# schematic.net
KiCad netlist of a schematic drawn in EasyEDA
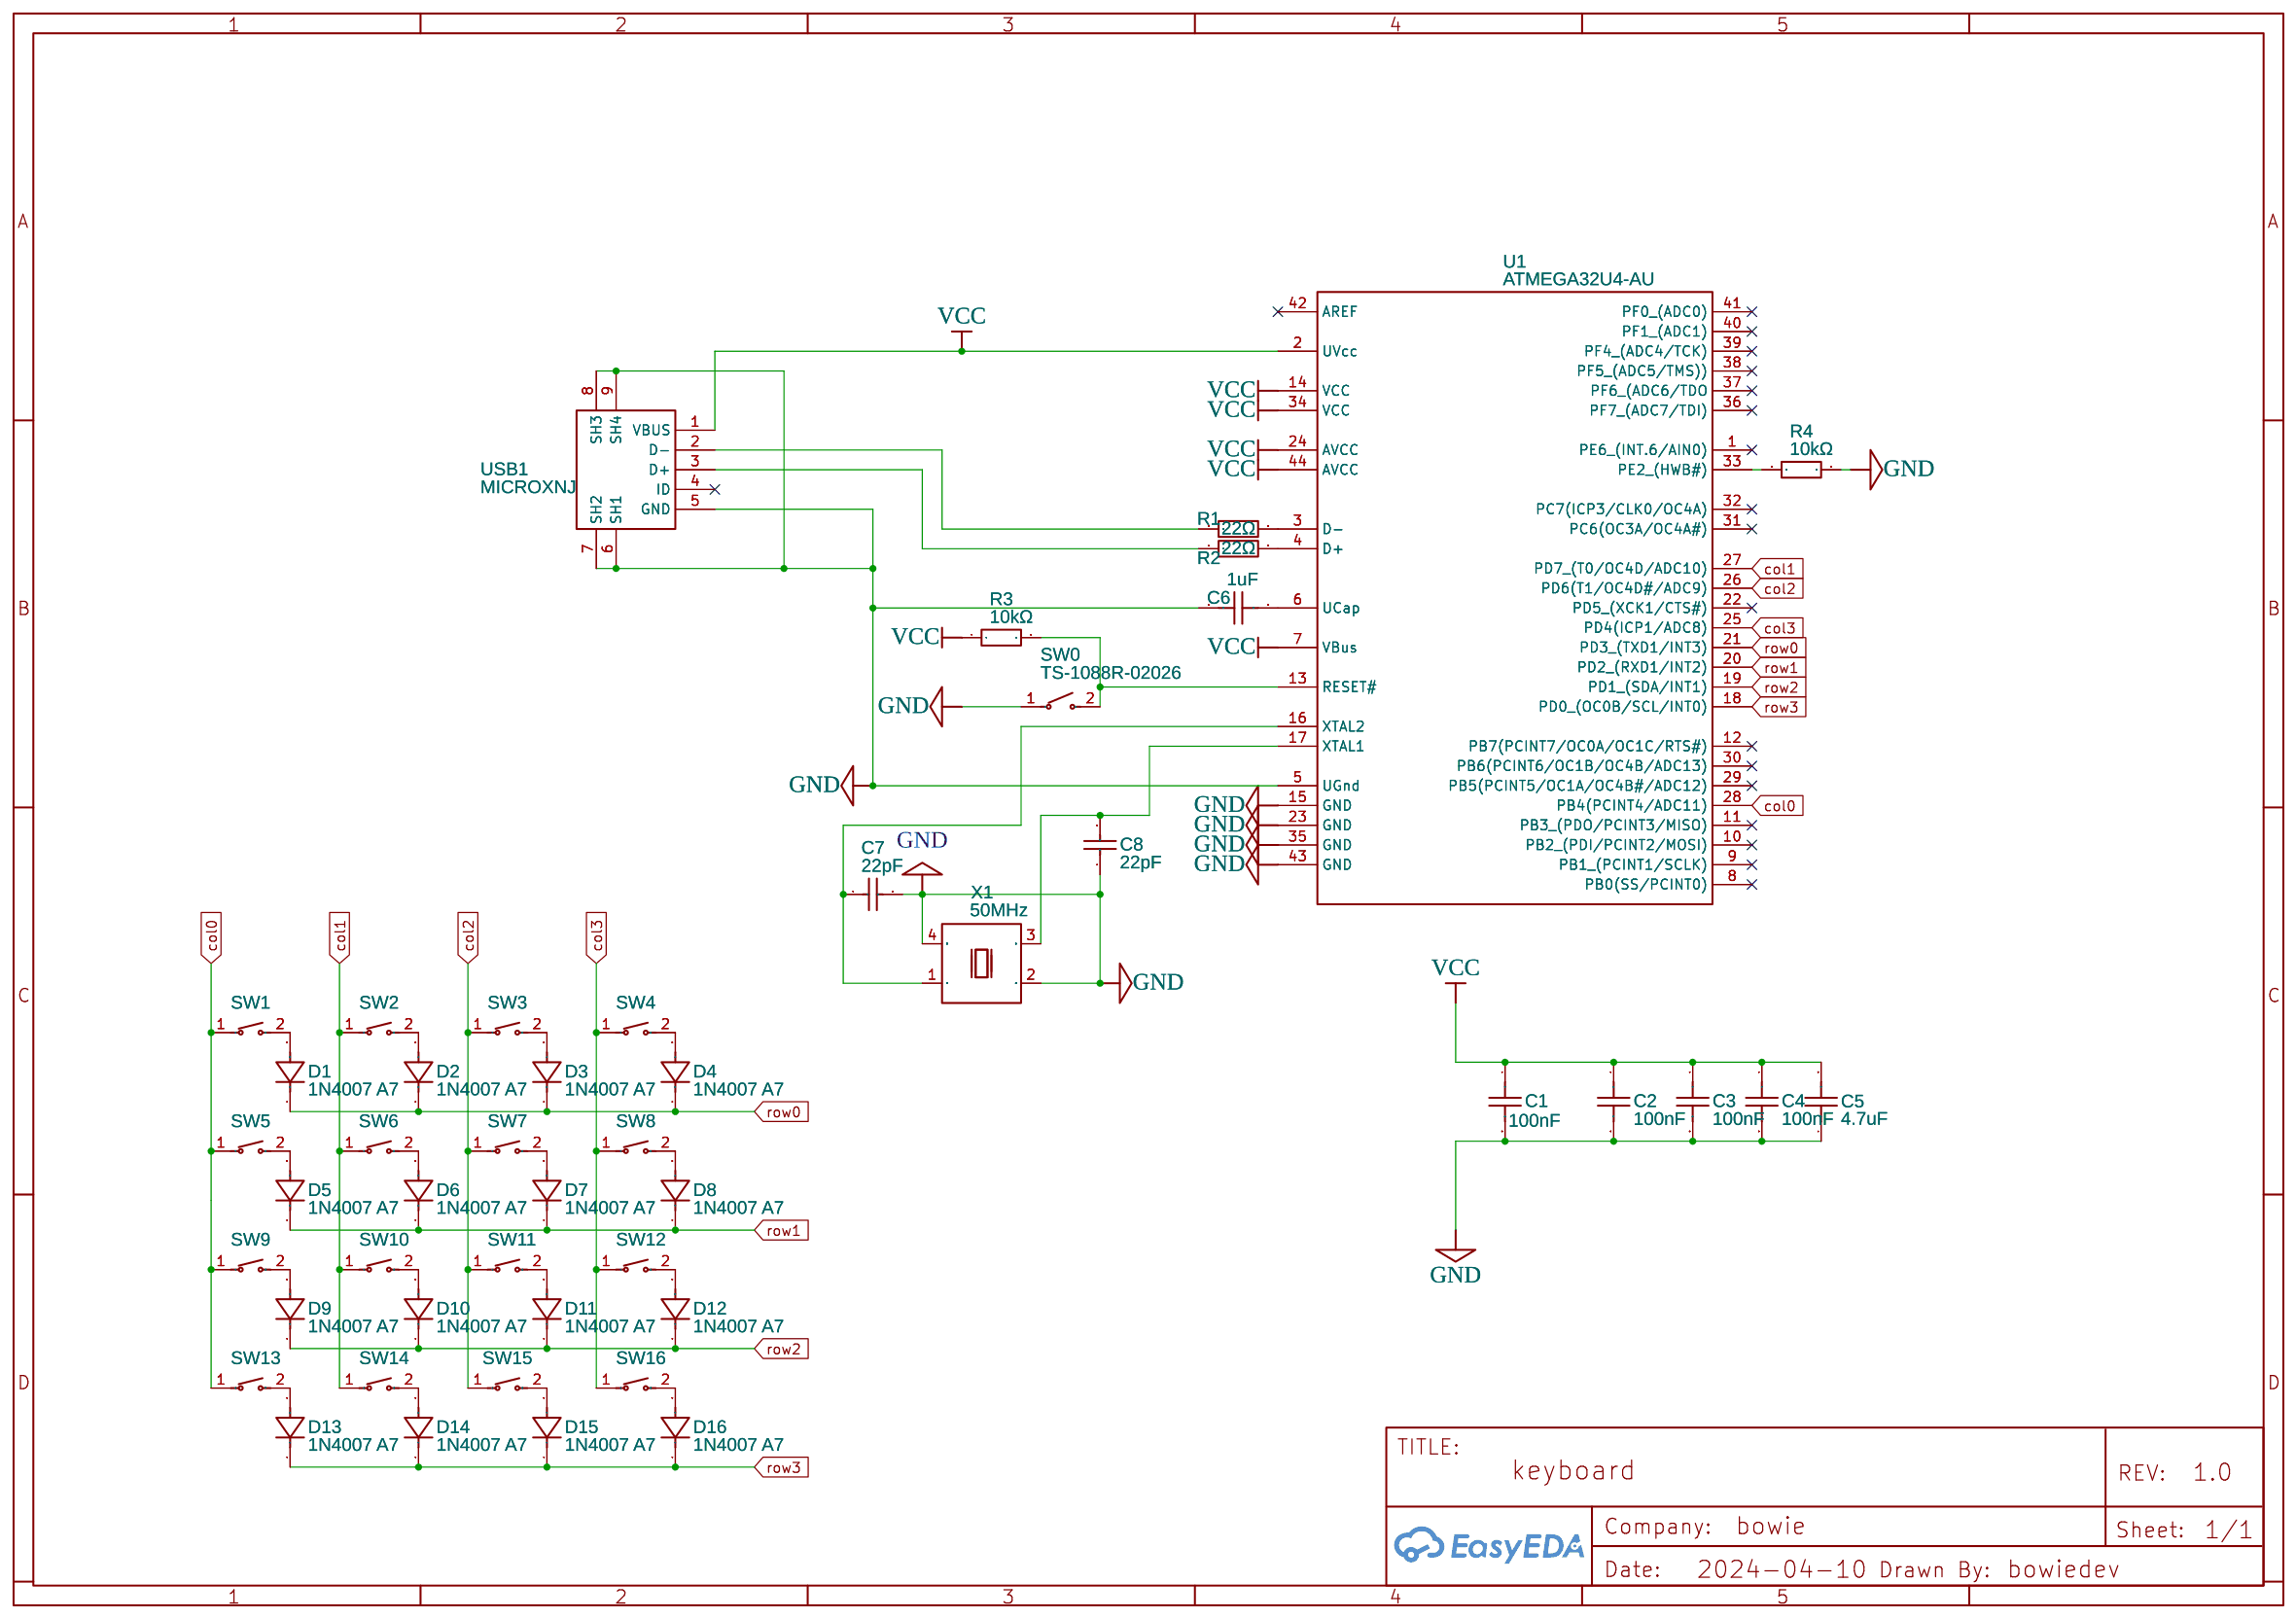
[diagram p0: schematic sheet]

(export (version "E")
  (design (tool "Eeschema 10.0.6"))
  (components
    (comp (ref "C1")
      (value "100nF")
      (fields (field (name "Manufacturer Part") "C1005X7R1C104KT000F") (field (name "Manufacturer") "TDK"))
      (libsource (lib "") (part "C1005X7R1C104KT000F"))
    )
    (comp (ref "C2")
      (value "100nF")
      (fields (field (name "Manufacturer Part") "C1005X7R1C104KT000F") (field (name "Manufacturer") "TDK"))
      (libsource (lib "") (part "C1005X7R1C104KT000F"))
    )
    (comp (ref "C3")
      (value "100nF")
      (fields (field (name "Manufacturer Part") "C1005X7R1C104KT000F") (field (name "Manufacturer") "TDK"))
      (libsource (lib "") (part "C1005X7R1C104KT000F"))
    )
    (comp (ref "C4")
      (value "100nF")
      (fields (field (name "Manufacturer Part") "C1005X7R1C104KT000F") (field (name "Manufacturer") "TDK"))
      (libsource (lib "") (part "C1005X7R1C104KT000F"))
    )
    (comp (ref "C5")
      (value "4.7uF")
      (fields
        (field (name "Manufacturer Part") "CS2012X5R475K500NRE")
        (field (name "Manufacturer") "SAMWHA(三和)")
      )
      (libsource (lib "") (part "CS2012X5R475K500NRE"))
    )
    (comp (ref "C6")
      (value "1uF")
      (fields
        (field (name "Manufacturer Part") "CS1608X7R105K250NRB")
        (field (name "Manufacturer") "SAMWHA(三和)")
      )
      (libsource (lib "") (part "CS1608X7R105K250NRB"))
    )
    (comp (ref "C7")
      (value "22pF")
      (fields (field (name "Manufacturer Part") "0402CG220J500NT") (field (name "Manufacturer") "FH(风华)"))
      (libsource (lib "") (part "0402CG220J500NT"))
    )
    (comp (ref "C8")
      (value "22pF")
      (fields (field (name "Manufacturer Part") "0402CG220J500NT") (field (name "Manufacturer") "FH(风华)"))
      (libsource (lib "") (part "0402CG220J500NT_1"))
    )
    (comp (ref "D1")
      (value "1N4007 A7")
      (fields (field (name "Manufacturer") "MSKSEMI(美森科)"))
      (libsource (lib "") (part "1N4007 A7"))
    )
    (comp (ref "D2")
      (value "1N4007 A7")
      (fields (field (name "Manufacturer") "MSKSEMI(美森科)"))
      (libsource (lib "") (part "1N4007 A7"))
    )
    (comp (ref "D3")
      (value "1N4007 A7")
      (fields (field (name "Manufacturer") "MSKSEMI(美森科)"))
      (libsource (lib "") (part "1N4007 A7"))
    )
    (comp (ref "D4")
      (value "1N4007 A7")
      (fields (field (name "Manufacturer") "MSKSEMI(美森科)"))
      (libsource (lib "") (part "1N4007 A7"))
    )
    (comp (ref "D5")
      (value "1N4007 A7")
      (fields (field (name "Manufacturer") "MSKSEMI(美森科)"))
      (libsource (lib "") (part "1N4007 A7"))
    )
    (comp (ref "D6")
      (value "1N4007 A7")
      (fields (field (name "Manufacturer") "MSKSEMI(美森科)"))
      (libsource (lib "") (part "1N4007 A7"))
    )
    (comp (ref "D7")
      (value "1N4007 A7")
      (fields (field (name "Manufacturer") "MSKSEMI(美森科)"))
      (libsource (lib "") (part "1N4007 A7"))
    )
    (comp (ref "D8")
      (value "1N4007 A7")
      (fields (field (name "Manufacturer") "MSKSEMI(美森科)"))
      (libsource (lib "") (part "1N4007 A7"))
    )
    (comp (ref "D9")
      (value "1N4007 A7")
      (fields (field (name "Manufacturer") "MSKSEMI(美森科)"))
      (libsource (lib "") (part "1N4007 A7"))
    )
    (comp (ref "D10")
      (value "1N4007 A7")
      (fields (field (name "Manufacturer") "MSKSEMI(美森科)"))
      (libsource (lib "") (part "1N4007 A7"))
    )
    (comp (ref "D11")
      (value "1N4007 A7")
      (fields (field (name "Manufacturer") "MSKSEMI(美森科)"))
      (libsource (lib "") (part "1N4007 A7"))
    )
    (comp (ref "D12")
      (value "1N4007 A7")
      (fields (field (name "Manufacturer") "MSKSEMI(美森科)"))
      (libsource (lib "") (part "1N4007 A7"))
    )
    (comp (ref "D13")
      (value "1N4007 A7")
      (fields (field (name "Manufacturer") "MSKSEMI(美森科)"))
      (libsource (lib "") (part "1N4007 A7"))
    )
    (comp (ref "D14")
      (value "1N4007 A7")
      (fields (field (name "Manufacturer") "MSKSEMI(美森科)"))
      (libsource (lib "") (part "1N4007 A7"))
    )
    (comp (ref "D15")
      (value "1N4007 A7")
      (fields (field (name "Manufacturer") "MSKSEMI(美森科)"))
      (libsource (lib "") (part "1N4007 A7"))
    )
    (comp (ref "D16")
      (value "1N4007 A7")
      (fields (field (name "Manufacturer") "MSKSEMI(美森科)"))
      (libsource (lib "") (part "1N4007 A7"))
    )
    (comp (ref "R1")
      (value "22Ω")
      (fields
        (field (name "Manufacturer Part") "0805W8J0220T5E")
        (field (name "Manufacturer") "UNI-ROYAL(厚声)")
      )
      (libsource (lib "") (part "0805W8J0220T5E"))
    )
    (comp (ref "R2")
      (value "22Ω")
      (fields
        (field (name "Manufacturer Part") "0805W8J0220T5E")
        (field (name "Manufacturer") "UNI-ROYAL(厚声)")
      )
      (libsource (lib "") (part "0805W8J0220T5E"))
    )
    (comp (ref "R3")
      (value "10kΩ")
      (fields
        (field (name "Manufacturer Part") "0805W8F1002T5E")
        (field (name "Manufacturer") "UNI-ROYAL(厚声)")
      )
      (libsource (lib "") (part "0805W8F1002T5E"))
    )
    (comp (ref "R4")
      (value "10kΩ")
      (fields
        (field (name "Manufacturer Part") "0805W8F1002T5E")
        (field (name "Manufacturer") "UNI-ROYAL(厚声)")
      )
      (libsource (lib "") (part "0805W8F1002T5E"))
    )
    (comp (ref "SW0")
      (value "TS-1088R-02026")
      (fields (field (name "Manufacturer") "XUNPU(讯普)"))
      (libsource (lib "") (part "TS-1088R-02026"))
    )
    (comp (ref "SW1")
      (value "CPG151101D93")
      (fields (field (name "Manufacturer") "Kailh(凯华)"))
      (libsource (lib "") (part "CPG151101D93"))
    )
    (comp (ref "SW2")
      (value "CPG151101D93")
      (fields (field (name "Manufacturer") "Kailh(凯华)"))
      (libsource (lib "") (part "CPG151101D93"))
    )
    (comp (ref "SW3")
      (value "CPG151101D93")
      (fields (field (name "Manufacturer") "Kailh(凯华)"))
      (libsource (lib "") (part "CPG151101D93"))
    )
    (comp (ref "SW4")
      (value "CPG151101D93")
      (fields (field (name "Manufacturer") "Kailh(凯华)"))
      (libsource (lib "") (part "CPG151101D93"))
    )
    (comp (ref "SW5")
      (value "CPG151101D93")
      (fields (field (name "Manufacturer") "Kailh(凯华)"))
      (libsource (lib "") (part "CPG151101D93"))
    )
    (comp (ref "SW6")
      (value "CPG151101D93")
      (fields (field (name "Manufacturer") "Kailh(凯华)"))
      (libsource (lib "") (part "CPG151101D93"))
    )
    (comp (ref "SW7")
      (value "CPG151101D93")
      (fields (field (name "Manufacturer") "Kailh(凯华)"))
      (libsource (lib "") (part "CPG151101D93"))
    )
    (comp (ref "SW8")
      (value "CPG151101D93")
      (fields (field (name "Manufacturer") "Kailh(凯华)"))
      (libsource (lib "") (part "CPG151101D93"))
    )
    (comp (ref "SW9")
      (value "CPG151101D93")
      (fields (field (name "Manufacturer") "Kailh(凯华)"))
      (libsource (lib "") (part "CPG151101D93"))
    )
    (comp (ref "SW10")
      (value "CPG151101D93")
      (fields (field (name "Manufacturer") "Kailh(凯华)"))
      (libsource (lib "") (part "CPG151101D93"))
    )
    (comp (ref "SW11")
      (value "CPG151101D93")
      (fields (field (name "Manufacturer") "Kailh(凯华)"))
      (libsource (lib "") (part "CPG151101D93"))
    )
    (comp (ref "SW12")
      (value "CPG151101D93")
      (fields (field (name "Manufacturer") "Kailh(凯华)"))
      (libsource (lib "") (part "CPG151101D93"))
    )
    (comp (ref "SW13")
      (value "CPG151101D93")
      (fields (field (name "Manufacturer") "Kailh(凯华)"))
      (libsource (lib "") (part "CPG151101D93"))
    )
    (comp (ref "SW14")
      (value "CPG151101D93")
      (fields (field (name "Manufacturer") "Kailh(凯华)"))
      (libsource (lib "") (part "CPG151101D93"))
    )
    (comp (ref "SW15")
      (value "CPG151101D93")
      (fields (field (name "Manufacturer") "Kailh(凯华)"))
      (libsource (lib "") (part "CPG151101D93"))
    )
    (comp (ref "SW16")
      (value "CPG151101D93")
      (fields (field (name "Manufacturer") "Kailh(凯华)"))
      (libsource (lib "") (part "CPG151101D93"))
    )
    (comp (ref "U1")
      (value "ATMEGA32U4-AU")
      (fields (field (name "Manufacturer") "MICROCHIP(美国微芯)"))
      (libsource (lib "") (part "ATMEGA32U4-AU"))
    )
    (comp (ref "USB1")
      (value "MICROXNJ")
      (fields (field (name "Manufacturer Part") "MicroXNJ") (field (name "Manufacturer") "SHOU HAN(首韩)"))
      (libsource (lib "") (part "MICROXNJ"))
    )
    (comp (ref "X1")
      (value "50MHz")
      (fields
        (field (name "Manufacturer Part") "OVETGLJTNF-50MHZ")
        (field (name "Manufacturer") "TAITIEN(泰艺电子)")
      )
      (libsource (lib "") (part "OVETGLJTNF-50MHZ"))
    )
  )
  (nets
    (net (code "1") (name "GND") (class "Default")
      (node (ref "C1") (pin "2") (pinfunction "2_2") (pintype "unspecified"))
      (node (ref "C2") (pin "2") (pinfunction "2_2") (pintype "unspecified"))
      (node (ref "C3") (pin "2") (pinfunction "2_2") (pintype "unspecified"))
      (node (ref "C4") (pin "2") (pinfunction "2_2") (pintype "unspecified"))
      (node (ref "C5") (pin "1") (pinfunction "1_1") (pintype "unspecified"))
      (node (ref "C6") (pin "1") (pinfunction "1_1") (pintype "unspecified"))
      (node (ref "C7") (pin "2") (pinfunction "2_2") (pintype "input"))
      (node (ref "C8") (pin "1") (pinfunction "1_1") (pintype "input"))
      (node (ref "R4") (pin "2") (pinfunction "2_2") (pintype "input"))
      (node (ref "SW0") (pin "1") (pinfunction "1_1") (pintype "unspecified"))
      (node (ref "U1") (pin "15") (pinfunction "GND_15") (pintype "passive"))
      (node (ref "U1") (pin "23") (pinfunction "GND_23") (pintype "passive"))
      (node (ref "U1") (pin "35") (pinfunction "GND_35") (pintype "passive"))
      (node (ref "U1") (pin "43") (pinfunction "GND_43") (pintype "passive"))
      (node (ref "U1") (pin "5") (pinfunction "UGnd_5") (pintype "passive"))
      (node (ref "USB1") (pin "5") (pinfunction "GND_5") (pintype "unspecified"))
      (node (ref "USB1") (pin "6") (pinfunction "SH1_6") (pintype "unspecified"))
      (node (ref "USB1") (pin "7") (pinfunction "SH2_7") (pintype "unspecified"))
      (node (ref "USB1") (pin "8") (pinfunction "SH3_8") (pintype "unspecified"))
      (node (ref "USB1") (pin "9") (pinfunction "SH4_9") (pintype "unspecified"))
      (node (ref "X1") (pin "2") (pinfunction "GND_2") (pintype "unspecified"))
      (node (ref "X1") (pin "4") (pinfunction "VCC_4") (pintype "unspecified"))
    )
    (net (code "2") (name "Net-(D1-A)") (class "Default")
      (node (ref "D1") (pin "2") (pinfunction "A_2") (pintype "unspecified"))
      (node (ref "SW1") (pin "2") (pinfunction "2_2") (pintype "unspecified"))
    )
    (net (code "3") (name "Net-(D2-A)") (class "Default")
      (node (ref "D2") (pin "2") (pinfunction "A_2") (pintype "unspecified"))
      (node (ref "SW2") (pin "2") (pinfunction "2_2") (pintype "unspecified"))
    )
    (net (code "4") (name "Net-(D3-A)") (class "Default")
      (node (ref "D3") (pin "2") (pinfunction "A_2") (pintype "unspecified"))
      (node (ref "SW3") (pin "2") (pinfunction "2_2") (pintype "unspecified"))
    )
    (net (code "5") (name "Net-(D4-A)") (class "Default")
      (node (ref "D4") (pin "2") (pinfunction "A_2") (pintype "unspecified"))
      (node (ref "SW4") (pin "2") (pinfunction "2_2") (pintype "unspecified"))
    )
    (net (code "6") (name "Net-(D5-A)") (class "Default")
      (node (ref "D5") (pin "2") (pinfunction "A_2") (pintype "unspecified"))
      (node (ref "SW5") (pin "2") (pinfunction "2_2") (pintype "unspecified"))
    )
    (net (code "7") (name "Net-(D6-A)") (class "Default")
      (node (ref "D6") (pin "2") (pinfunction "A_2") (pintype "unspecified"))
      (node (ref "SW6") (pin "2") (pinfunction "2_2") (pintype "unspecified"))
    )
    (net (code "8") (name "Net-(D7-A)") (class "Default")
      (node (ref "D7") (pin "2") (pinfunction "A_2") (pintype "unspecified"))
      (node (ref "SW7") (pin "2") (pinfunction "2_2") (pintype "unspecified"))
    )
    (net (code "9") (name "Net-(D8-A)") (class "Default")
      (node (ref "D8") (pin "2") (pinfunction "A_2") (pintype "unspecified"))
      (node (ref "SW8") (pin "2") (pinfunction "2_2") (pintype "unspecified"))
    )
    (net (code "10") (name "Net-(D9-A)") (class "Default")
      (node (ref "D9") (pin "2") (pinfunction "A_2") (pintype "unspecified"))
      (node (ref "SW9") (pin "2") (pinfunction "2_2") (pintype "unspecified"))
    )
    (net (code "11") (name "Net-(D10-A)") (class "Default")
      (node (ref "D10") (pin "2") (pinfunction "A_2") (pintype "unspecified"))
      (node (ref "SW10") (pin "2") (pinfunction "2_2") (pintype "unspecified"))
    )
    (net (code "12") (name "Net-(D11-A)") (class "Default")
      (node (ref "D11") (pin "2") (pinfunction "A_2") (pintype "unspecified"))
      (node (ref "SW11") (pin "2") (pinfunction "2_2") (pintype "unspecified"))
    )
    (net (code "13") (name "Net-(D12-A)") (class "Default")
      (node (ref "D12") (pin "2") (pinfunction "A_2") (pintype "unspecified"))
      (node (ref "SW12") (pin "2") (pinfunction "2_2") (pintype "unspecified"))
    )
    (net (code "14") (name "Net-(D13-A)") (class "Default")
      (node (ref "D13") (pin "2") (pinfunction "A_2") (pintype "unspecified"))
      (node (ref "SW13") (pin "2") (pinfunction "2_2") (pintype "unspecified"))
    )
    (net (code "15") (name "Net-(D14-A)") (class "Default")
      (node (ref "D14") (pin "2") (pinfunction "A_2") (pintype "unspecified"))
      (node (ref "SW14") (pin "2") (pinfunction "2_2") (pintype "unspecified"))
    )
    (net (code "16") (name "Net-(D15-A)") (class "Default")
      (node (ref "D15") (pin "2") (pinfunction "A_2") (pintype "unspecified"))
      (node (ref "SW15") (pin "2") (pinfunction "2_2") (pintype "unspecified"))
    )
    (net (code "17") (name "Net-(D16-A)") (class "Default")
      (node (ref "D16") (pin "2") (pinfunction "A_2") (pintype "unspecified"))
      (node (ref "SW16") (pin "2") (pinfunction "2_2") (pintype "unspecified"))
    )
    (net (code "18") (name "Net-(U1-D+)") (class "Default")
      (node (ref "R2") (pin "2") (pinfunction "2_2") (pintype "input"))
      (node (ref "U1") (pin "4") (pinfunction "D+_4") (pintype "bidirectional"))
    )
    (net (code "19") (name "Net-(U1-D-)") (class "Default")
      (node (ref "R1") (pin "2") (pinfunction "2_2") (pintype "input"))
      (node (ref "U1") (pin "3") (pinfunction "D-_3") (pintype "bidirectional"))
    )
    (net (code "20") (name "Net-(U1-PE2_(HWB#))") (class "Default")
      (node (ref "R4") (pin "1") (pinfunction "1_1") (pintype "input"))
      (node (ref "U1") (pin "33") (pinfunction "PE2_(HWB#)_33") (pintype "bidirectional"))
    )
    (net (code "21") (name "Net-(U1-RESET#)") (class "Default")
      (node (ref "R3") (pin "2") (pinfunction "2_2") (pintype "input"))
      (node (ref "SW0") (pin "2") (pinfunction "2_2") (pintype "unspecified"))
      (node (ref "U1") (pin "13") (pinfunction "RESET#_13") (pintype "unspecified"))
    )
    (net (code "22") (name "Net-(U1-UCap)") (class "Default")
      (node (ref "C6") (pin "2") (pinfunction "2_2") (pintype "unspecified"))
      (node (ref "U1") (pin "6") (pinfunction "UCap_6") (pintype "unspecified"))
    )
    (net (code "23") (name "Net-(U1-XTAL1)") (class "Default")
      (node (ref "C8") (pin "2") (pinfunction "2_2") (pintype "input"))
      (node (ref "U1") (pin "17") (pinfunction "XTAL1_17") (pintype "unspecified"))
      (node (ref "X1") (pin "3") (pinfunction "OUT_3") (pintype "unspecified"))
    )
    (net (code "24") (name "Net-(U1-XTAL2)") (class "Default")
      (node (ref "C7") (pin "1") (pinfunction "1_1") (pintype "input"))
      (node (ref "U1") (pin "16") (pinfunction "XTAL2_16") (pintype "output"))
      (node (ref "X1") (pin "1") (pinfunction "tri_1") (pintype "unspecified"))
    )
    (net (code "25") (name "Net-(USB1-D+)") (class "Default")
      (node (ref "R2") (pin "1") (pinfunction "1_1") (pintype "input"))
      (node (ref "USB1") (pin "3") (pinfunction "D+_3") (pintype "unspecified"))
    )
    (net (code "26") (name "Net-(USB1-D-)") (class "Default")
      (node (ref "R1") (pin "1") (pinfunction "1_1") (pintype "input"))
      (node (ref "USB1") (pin "2") (pinfunction "D-_2") (pintype "unspecified"))
    )
    (net (code "27") (name "VCC") (class "Default")
      (node (ref "C1") (pin "1") (pinfunction "1_1") (pintype "unspecified"))
      (node (ref "C2") (pin "1") (pinfunction "1_1") (pintype "unspecified"))
      (node (ref "C3") (pin "1") (pinfunction "1_1") (pintype "unspecified"))
      (node (ref "C4") (pin "1") (pinfunction "1_1") (pintype "unspecified"))
      (node (ref "C5") (pin "2") (pinfunction "2_2") (pintype "unspecified"))
      (node (ref "R3") (pin "1") (pinfunction "1_1") (pintype "input"))
      (node (ref "U1") (pin "14") (pinfunction "VCC_14") (pintype "passive"))
      (node (ref "U1") (pin "2") (pinfunction "UVcc_2") (pintype "passive"))
      (node (ref "U1") (pin "24") (pinfunction "AVCC_24") (pintype "passive"))
      (node (ref "U1") (pin "34") (pinfunction "VCC_34") (pintype "passive"))
      (node (ref "U1") (pin "44") (pinfunction "AVCC_44") (pintype "passive"))
      (node (ref "U1") (pin "7") (pinfunction "VBus_7") (pintype "unspecified"))
      (node (ref "USB1") (pin "1") (pinfunction "VBUS_1") (pintype "unspecified"))
    )
    (net (code "28") (name "col0") (class "Default")
      (node (ref "SW1") (pin "1") (pinfunction "1_1") (pintype "unspecified"))
      (node (ref "SW13") (pin "1") (pinfunction "1_1") (pintype "unspecified"))
      (node (ref "SW5") (pin "1") (pinfunction "1_1") (pintype "unspecified"))
      (node (ref "SW9") (pin "1") (pinfunction "1_1") (pintype "unspecified"))
      (node (ref "U1") (pin "28") (pinfunction "PB4(PCINT4/ADC11)_28") (pintype "bidirectional"))
    )
    (net (code "29") (name "col1") (class "Default")
      (node (ref "SW10") (pin "1") (pinfunction "1_1") (pintype "unspecified"))
      (node (ref "SW14") (pin "1") (pinfunction "1_1") (pintype "unspecified"))
      (node (ref "SW2") (pin "1") (pinfunction "1_1") (pintype "unspecified"))
      (node (ref "SW6") (pin "1") (pinfunction "1_1") (pintype "unspecified"))
      (node (ref "U1") (pin "27") (pinfunction "PD7_(T0/OC4D/ADC10)_27") (pintype "bidirectional"))
    )
    (net (code "30") (name "col2") (class "Default")
      (node (ref "SW11") (pin "1") (pinfunction "1_1") (pintype "unspecified"))
      (node (ref "SW15") (pin "1") (pinfunction "1_1") (pintype "unspecified"))
      (node (ref "SW3") (pin "1") (pinfunction "1_1") (pintype "unspecified"))
      (node (ref "SW7") (pin "1") (pinfunction "1_1") (pintype "unspecified"))
      (node (ref "U1") (pin "26") (pinfunction "PD6(T1/OC4D#/ADC9)_26") (pintype "bidirectional"))
    )
    (net (code "31") (name "col3") (class "Default")
      (node (ref "SW12") (pin "1") (pinfunction "1_1") (pintype "unspecified"))
      (node (ref "SW16") (pin "1") (pinfunction "1_1") (pintype "unspecified"))
      (node (ref "SW4") (pin "1") (pinfunction "1_1") (pintype "unspecified"))
      (node (ref "SW8") (pin "1") (pinfunction "1_1") (pintype "unspecified"))
      (node (ref "U1") (pin "25") (pinfunction "PD4(ICP1/ADC8)_25") (pintype "bidirectional"))
    )
    (net (code "32") (name "row0") (class "Default")
      (node (ref "D1") (pin "1") (pinfunction "K_1") (pintype "unspecified"))
      (node (ref "D2") (pin "1") (pinfunction "K_1") (pintype "unspecified"))
      (node (ref "D3") (pin "1") (pinfunction "K_1") (pintype "unspecified"))
      (node (ref "D4") (pin "1") (pinfunction "K_1") (pintype "unspecified"))
      (node (ref "U1") (pin "21") (pinfunction "PD3_(TXD1/INT3)_21") (pintype "bidirectional"))
    )
    (net (code "33") (name "row1") (class "Default")
      (node (ref "D5") (pin "1") (pinfunction "K_1") (pintype "unspecified"))
      (node (ref "D6") (pin "1") (pinfunction "K_1") (pintype "unspecified"))
      (node (ref "D7") (pin "1") (pinfunction "K_1") (pintype "unspecified"))
      (node (ref "D8") (pin "1") (pinfunction "K_1") (pintype "unspecified"))
      (node (ref "U1") (pin "20") (pinfunction "PD2_(RXD1/INT2)_20") (pintype "bidirectional"))
    )
    (net (code "34") (name "row2") (class "Default")
      (node (ref "D10") (pin "1") (pinfunction "K_1") (pintype "unspecified"))
      (node (ref "D11") (pin "1") (pinfunction "K_1") (pintype "unspecified"))
      (node (ref "D12") (pin "1") (pinfunction "K_1") (pintype "unspecified"))
      (node (ref "D9") (pin "1") (pinfunction "K_1") (pintype "unspecified"))
      (node (ref "U1") (pin "19") (pinfunction "PD1_(SDA/INT1)_19") (pintype "bidirectional"))
    )
    (net (code "35") (name "row3") (class "Default")
      (node (ref "D13") (pin "1") (pinfunction "K_1") (pintype "unspecified"))
      (node (ref "D14") (pin "1") (pinfunction "K_1") (pintype "unspecified"))
      (node (ref "D15") (pin "1") (pinfunction "K_1") (pintype "unspecified"))
      (node (ref "D16") (pin "1") (pinfunction "K_1") (pintype "unspecified"))
      (node (ref "U1") (pin "18") (pinfunction "PD0_(OC0B/SCL/INT0)_18") (pintype "bidirectional"))
    )
    (net (code "36") (name "unconnected-(U1-AREF-Pad42)") (class "Default")
      (node (ref "U1") (pin "42") (pinfunction "AREF_42") (pintype "unspecified+no_connect"))
    )
    (net (code "37") (name "unconnected-(U1-PB0(SS{slash}PCINT0)-Pad8)") (class "Default")
      (node (ref "U1") (pin "8") (pinfunction "PB0(SS/PCINT0)_8") (pintype "bidirectional+no_connect"))
    )
    (net (code "38") (name "unconnected-(U1-PB1_(PCINT1{slash}SCLK)-Pad9)") (class "Default")
      (node (ref "U1") (pin "9") (pinfunction "PB1_(PCINT1/SCLK)_9") (pintype "bidirectional+no_connect"))
    )
    (net (code "39") (name "unconnected-(U1-PB2_(PDI{slash}PCINT2{slash}MOSI)-Pad10)") (class "Default")
      (node (ref "U1") (pin "10") (pinfunction "PB2_(PDI/PCINT2/MOSI)_10") (pintype "bidirectional+no_connect"))
    )
    (net (code "40") (name "unconnected-(U1-PB3_(PDO{slash}PCINT3{slash}MISO)-Pad11)") (class "Default")
      (node (ref "U1") (pin "11") (pinfunction "PB3_(PDO/PCINT3/MISO)_11") (pintype "bidirectional+no_connect"))
    )
    (net (code "41") (name "unconnected-(U1-PB5(PCINT5{slash}OC1A{slash}OC4B#{slash}ADC12)-Pad29)") (class "Default")
      (node (ref "U1") (pin "29") (pinfunction "PB5(PCINT5/OC1A/OC4B#/ADC12)_29") (pintype "bidirectional+no_connect"))
    )
    (net (code "42") (name "unconnected-(U1-PB6(PCINT6{slash}OC1B{slash}OC4B{slash}ADC13)-Pad30)") (class "Default")
      (node (ref "U1") (pin "30") (pinfunction "PB6(PCINT6/OC1B/OC4B/ADC13)_30") (pintype "bidirectional+no_connect"))
    )
    (net (code "43") (name "unconnected-(U1-PB7(PCINT7{slash}OC0A{slash}OC1C{slash}RTS#)-Pad12)") (class "Default")
      (node (ref "U1") (pin "12") (pinfunction "PB7(PCINT7/OC0A/OC1C/RTS#)_12") (pintype "bidirectional+no_connect"))
    )
    (net (code "44") (name "unconnected-(U1-PC6(OC3A{slash}OC4A#)-Pad31)") (class "Default")
      (node (ref "U1") (pin "31") (pinfunction "PC6(OC3A/OC4A#)_31") (pintype "bidirectional+no_connect"))
    )
    (net (code "45") (name "unconnected-(U1-PC7(ICP3{slash}CLK0{slash}OC4A)-Pad32)") (class "Default")
      (node (ref "U1") (pin "32") (pinfunction "PC7(ICP3/CLK0/OC4A)_32") (pintype "bidirectional+no_connect"))
    )
    (net (code "46") (name "unconnected-(U1-PD5_(XCK1{slash}CTS#)-Pad22)") (class "Default")
      (node (ref "U1") (pin "22") (pinfunction "PD5_(XCK1/CTS#)_22") (pintype "bidirectional+no_connect"))
    )
    (net (code "47") (name "unconnected-(U1-PE6_(INT.6{slash}AIN0)-Pad1)") (class "Default")
      (node (ref "U1") (pin "1") (pinfunction "PE6_(INT.6/AIN0)_1") (pintype "bidirectional+no_connect"))
    )
    (net (code "48") (name "unconnected-(U1-PF0_(ADC0)-Pad41)") (class "Default")
      (node (ref "U1") (pin "41") (pinfunction "PF0_(ADC0)_41") (pintype "bidirectional+no_connect"))
    )
    (net (code "49") (name "unconnected-(U1-PF1_(ADC1)-Pad40)") (class "Default")
      (node (ref "U1") (pin "40") (pinfunction "PF1_(ADC1)_40") (pintype "bidirectional+no_connect"))
    )
    (net (code "50") (name "unconnected-(U1-PF4_(ADC4{slash}TCK)-Pad39)") (class "Default")
      (node (ref "U1") (pin "39") (pinfunction "PF4_(ADC4/TCK)_39") (pintype "bidirectional+no_connect"))
    )
    (net (code "51") (name "unconnected-(U1-PF5_(ADC5{slash}TMS))-Pad38)") (class "Default")
      (node (ref "U1") (pin "38") (pinfunction "PF5_(ADC5/TMS))_38") (pintype "bidirectional+no_connect"))
    )
    (net (code "52") (name "unconnected-(U1-PF6_(ADC6{slash}TDO-Pad37)") (class "Default")
      (node (ref "U1") (pin "37") (pinfunction "PF6_(ADC6/TDO_37") (pintype "bidirectional+no_connect"))
    )
    (net (code "53") (name "unconnected-(U1-PF7_(ADC7{slash}TDI)-Pad36)") (class "Default")
      (node (ref "U1") (pin "36") (pinfunction "PF7_(ADC7/TDI)_36") (pintype "bidirectional+no_connect"))
    )
    (net (code "54") (name "unconnected-(USB1-ID-Pad4)") (class "Default")
      (node (ref "USB1") (pin "4") (pinfunction "ID_4") (pintype "unspecified+no_connect"))
    )
  )
)
